# SD_LAN.net
KiCad netlist of a schematic drawn in Altium Designer
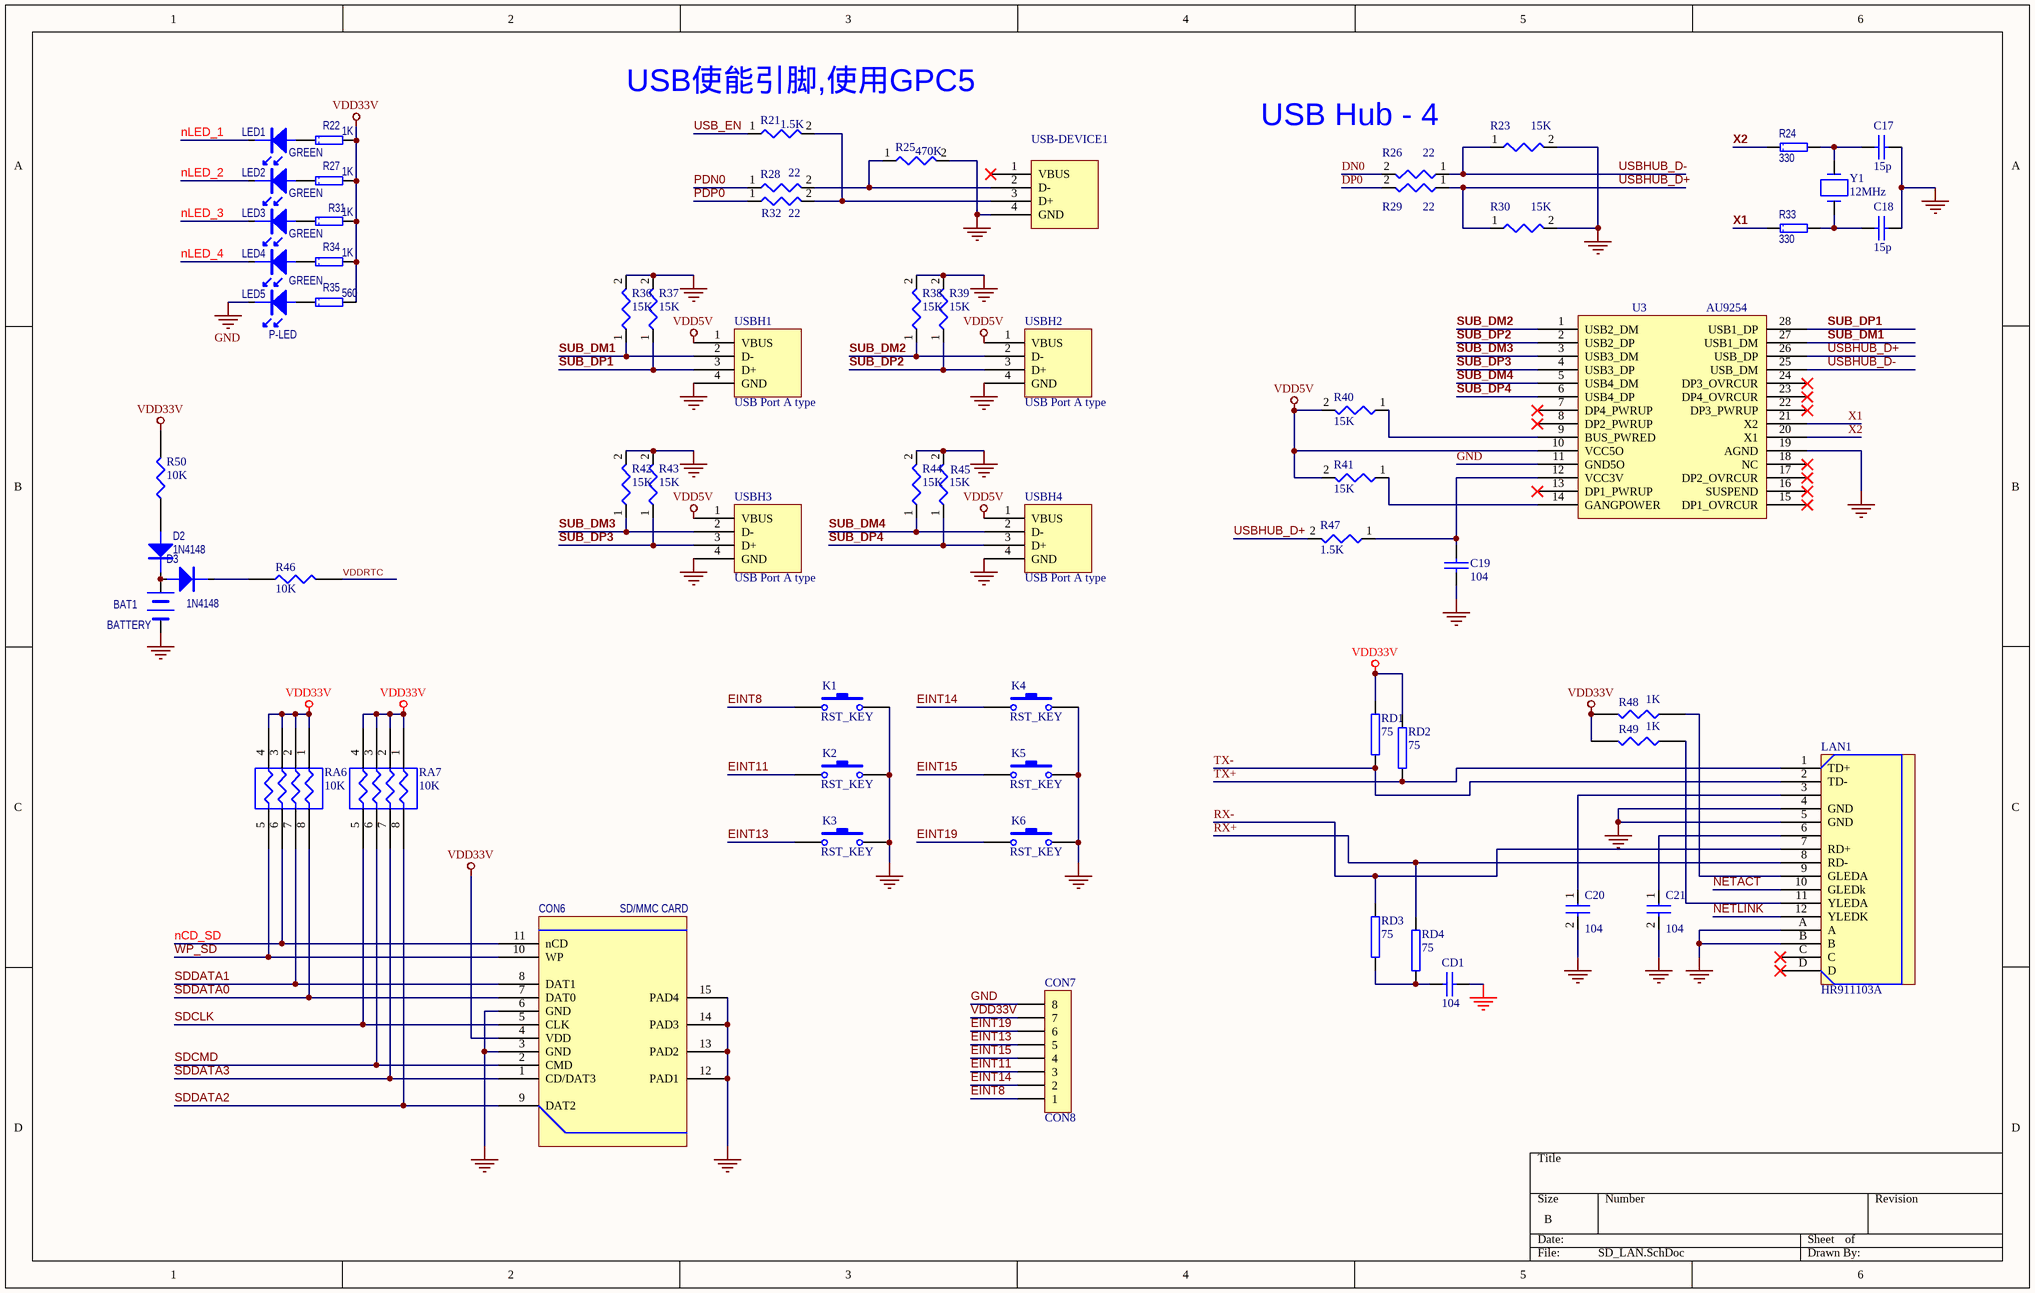
[diagram p0: SD_LAN.SchDoc]

(export (version "E")
  (design (tool "Eeschema 10.0.6"))
  (components
    (comp (ref "BAT1") (value "BATTERY") (footprint "BATT") (libsource (lib "*") (part "BATTERY")))
    (comp (ref "C17") (value "15p") (footprint "0603A") (libsource (lib "*") (part "CAP")))
    (comp (ref "C18") (value "15p") (footprint "0603A") (libsource (lib "*") (part "CAP")))
    (comp (ref "C19") (value "104") (footprint "0603A") (libsource (lib "*") (part "CAP")))
    (comp (ref "C20") (value "104") (footprint "0603A") (libsource (lib "*") (part "CAP NP_0")))
    (comp (ref "C21") (value "104") (footprint "0603A") (libsource (lib "*") (part "CAP NP_0")))
    (comp (ref "CD1") (value "104") (footprint "0603A") (libsource (lib "*") (part "CAP")))
    (comp (ref "CON6") (value "SD/MMC CARD") (footprint "SDCARD") (libsource (lib "*") (part "SD")))
    (comp (ref "CON7")
      (value "CON8")
      (footprint "SMD8")
      (description "Connector")
      (libsource (lib "*") (part "CON8"))
    )
    (comp (ref "D2") (value "1N4148") (footprint "D1206") (libsource (lib "*") (part "DIODE")))
    (comp (ref "D3") (value "1N4148") (footprint "D1206") (libsource (lib "*") (part "DIODE")))
    (comp (ref "K1")
      (value "RST_KEY")
      (footprint "SW-PB2")
      (description "Switch")
      (fields (field (name "PUBLISHER") "Altium Limited"))
      (libsource (lib "Miscellaneous Devices") (part "SW-PB"))
    )
    (comp (ref "K2")
      (value "RST_KEY")
      (footprint "SW-PB2")
      (description "Switch")
      (fields (field (name "PUBLISHER") "Altium Limited"))
      (libsource (lib "Miscellaneous Devices") (part "SW-PB"))
    )
    (comp (ref "K3")
      (value "RST_KEY")
      (footprint "SW-PB2")
      (description "Switch")
      (fields (field (name "PUBLISHER") "Altium Limited"))
      (libsource (lib "Miscellaneous Devices") (part "SW-PB"))
    )
    (comp (ref "K4")
      (value "RST_KEY")
      (footprint "SW-PB2")
      (description "Switch")
      (fields (field (name "PUBLISHER") "Altium Limited"))
      (libsource (lib "Miscellaneous Devices") (part "SW-PB"))
    )
    (comp (ref "K5")
      (value "RST_KEY")
      (footprint "SW-PB2")
      (description "Switch")
      (fields (field (name "PUBLISHER") "Altium Limited"))
      (libsource (lib "Miscellaneous Devices") (part "SW-PB"))
    )
    (comp (ref "K6")
      (value "RST_KEY")
      (footprint "SW-PB2")
      (description "Switch")
      (fields (field (name "PUBLISHER") "Altium Limited"))
      (libsource (lib "Miscellaneous Devices") (part "SW-PB"))
    )
    (comp (ref "LAN1") (value "HR911103A") (footprint "HR911103A") (libsource (lib "*") (part "HR911103A")))
    (comp (ref "LED1") (value "GREEN") (footprint "LED") (libsource (lib "*") (part "LED")))
    (comp (ref "LED2") (value "GREEN") (footprint "LED") (libsource (lib "*") (part "LED")))
    (comp (ref "LED3") (value "GREEN") (footprint "LED") (libsource (lib "*") (part "LED")))
    (comp (ref "LED4") (value "GREEN") (footprint "LED") (libsource (lib "*") (part "LED")))
    (comp (ref "LED5") (value "P-LED") (footprint "LED") (libsource (lib "*") (part "LED")))
    (comp (ref "R21") (value "1.5K") (footprint "0603R") (libsource (lib "*") (part "RESISTOR_2")))
    (comp (ref "R22") (value "1K") (footprint "0603R") (libsource (lib "*") (part "RES")))
    (comp (ref "R23") (value "15K") (footprint "0603R") (libsource (lib "*") (part "RESISTOR_2")))
    (comp (ref "R24") (value "330") (footprint "0603R") (libsource (lib "*") (part "RES")))
    (comp (ref "R25") (value "470K") (footprint "0603R") (libsource (lib "*") (part "RESISTOR_2")))
    (comp (ref "R26") (value "22") (footprint "0603R") (libsource (lib "*") (part "RESISTOR_2")))
    (comp (ref "R27") (value "1K") (footprint "0603R") (libsource (lib "*") (part "RES")))
    (comp (ref "R28") (value "22") (footprint "0603R") (libsource (lib "*") (part "RESISTOR_2")))
    (comp (ref "R29") (value "22") (footprint "0603R") (libsource (lib "*") (part "RESISTOR_2")))
    (comp (ref "R30") (value "15K") (footprint "0603R") (libsource (lib "*") (part "RESISTOR_2")))
    (comp (ref "R31") (value "1K") (footprint "0603R") (libsource (lib "*") (part "RES")))
    (comp (ref "R32") (value "22") (footprint "0603R") (libsource (lib "*") (part "RESISTOR_2")))
    (comp (ref "R33") (value "330") (footprint "0603R") (libsource (lib "*") (part "RES")))
    (comp (ref "R34") (value "1K") (footprint "0603R") (libsource (lib "*") (part "RES")))
    (comp (ref "R35") (value "560") (footprint "0603R") (libsource (lib "*") (part "RES")))
    (comp (ref "R36") (value "15K") (footprint "0603R") (libsource (lib "*") (part "RESISTOR_2")))
    (comp (ref "R37") (value "15K") (footprint "0603R") (libsource (lib "*") (part "RESISTOR_2")))
    (comp (ref "R38") (value "15K") (footprint "0603R") (libsource (lib "*") (part "RESISTOR_2")))
    (comp (ref "R39") (value "15K") (footprint "0603R") (libsource (lib "*") (part "RESISTOR_2")))
    (comp (ref "R40") (value "15K") (footprint "0603R") (libsource (lib "*") (part "RESISTOR_2")))
    (comp (ref "R41") (value "15K") (footprint "0603R") (libsource (lib "*") (part "RESISTOR_2")))
    (comp (ref "R42") (value "15K") (footprint "0603R") (libsource (lib "*") (part "RESISTOR_2")))
    (comp (ref "R43") (value "15K") (footprint "0603R") (libsource (lib "*") (part "RESISTOR_2")))
    (comp (ref "R44") (value "15K") (footprint "0603R") (libsource (lib "*") (part "RESISTOR_2")))
    (comp (ref "R45") (value "15K") (footprint "0603R") (libsource (lib "*") (part "RESISTOR_2")))
    (comp (ref "R46") (value "10K") (footprint "0603R") (libsource (lib "*") (part "RES1")))
    (comp (ref "R47") (value "1.5K") (footprint "0603R") (libsource (lib "*") (part "RESISTOR_2")))
    (comp (ref "R48") (value "1K") (footprint "0603R") (libsource (lib "*") (part "RES1")))
    (comp (ref "R49") (value "1K") (footprint "0603R") (libsource (lib "*") (part "RES1")))
    (comp (ref "R50") (value "10K") (footprint "0603R") (libsource (lib "*") (part "RES1")))
    (comp (ref "RA6") (value "10K") (footprint "R-AR4") (libsource (lib "*") (part "RP4R")))
    (comp (ref "RA7") (value "10K") (footprint "R-AR4") (libsource (lib "*") (part "RP4R")))
    (comp (ref "RD1") (value "75") (footprint "0603R") (libsource (lib "*") (part "RES2")))
    (comp (ref "RD2") (value "75") (footprint "0603R") (libsource (lib "*") (part "RES2")))
    (comp (ref "RD3") (value "75") (footprint "0603R") (libsource (lib "*") (part "RES2")))
    (comp (ref "RD4") (value "75") (footprint "0603R") (libsource (lib "*") (part "RES2")))
    (comp (ref "U3") (value "AU9254") (footprint "AU9254") (libsource (lib "*") (part "USBHUB")))
    (comp (ref "USB-DEVICE1")
      (value "USB Port A type")
      (footprint "USB-B")
      (libsource (lib "*") (part "USBPORT"))
    )
    (comp (ref "USBH1") (value "USB Port A type") (footprint "USB-A") (libsource (lib "*") (part "USBPORT")))
    (comp (ref "USBH2") (value "USB Port A type") (footprint "USB-A") (libsource (lib "*") (part "USBPORT")))
    (comp (ref "USBH3") (value "USB Port A type") (footprint "USB-A") (libsource (lib "*") (part "USBPORT")))
    (comp (ref "USBH4") (value "USB Port A type") (footprint "USB-A") (libsource (lib "*") (part "USBPORT")))
    (comp (ref "Y1") (value "12MHz") (footprint "OSC2PR-1") (libsource (lib "*") (part "CRYSTAL")))
  )
  (nets
    (net (code "1") (name "/DN0") (class "Default")
      (node (ref "R26") (pin "2") (pinfunction "2_2") (pintype "passive"))
    )
    (net (code "2") (name "/DP0") (class "Default")
      (node (ref "R29") (pin "2") (pinfunction "2_2") (pintype "passive"))
    )
    (net (code "3") (name "/EINT8") (class "Default")
      (node (ref "CON7") (pin "1") (pinfunction "1_1") (pintype "passive"))
      (node (ref "K1") (pin "1") (pinfunction "1_1") (pintype "passive"))
    )
    (net (code "4") (name "/EINT11") (class "Default")
      (node (ref "CON7") (pin "3") (pinfunction "3_3") (pintype "passive"))
      (node (ref "K2") (pin "1") (pinfunction "1_1") (pintype "passive"))
    )
    (net (code "5") (name "/EINT13") (class "Default")
      (node (ref "CON7") (pin "5") (pinfunction "5_5") (pintype "passive"))
      (node (ref "K3") (pin "1") (pinfunction "1_1") (pintype "passive"))
    )
    (net (code "6") (name "/EINT14") (class "Default")
      (node (ref "CON7") (pin "2") (pinfunction "2_2") (pintype "passive"))
      (node (ref "K4") (pin "1") (pinfunction "1_1") (pintype "passive"))
    )
    (net (code "7") (name "/EINT15") (class "Default")
      (node (ref "CON7") (pin "4") (pinfunction "4_4") (pintype "passive"))
      (node (ref "K5") (pin "1") (pinfunction "1_1") (pintype "passive"))
    )
    (net (code "8") (name "/EINT19") (class "Default")
      (node (ref "CON7") (pin "6") (pinfunction "6_6") (pintype "passive"))
      (node (ref "K6") (pin "1") (pinfunction "1_1") (pintype "passive"))
    )
    (net (code "9") (name "/NETACT") (class "Default")
      (node (ref "LAN1") (pin "10") (pinfunction "GLEDk_10") (pintype "passive"))
    )
    (net (code "10") (name "/NETLINK") (class "Default")
      (node (ref "LAN1") (pin "12") (pinfunction "YLEDK_12") (pintype "passive"))
    )
    (net (code "11") (name "/PDN0") (class "Default")
      (node (ref "R28") (pin "1") (pinfunction "1_1") (pintype "passive"))
    )
    (net (code "12") (name "/PDP0") (class "Default")
      (node (ref "R32") (pin "1") (pinfunction "1_1") (pintype "passive"))
    )
    (net (code "13") (name "/RX+") (class "Default")
      (node (ref "LAN1") (pin "8") (pinfunction "RD-_8") (pintype "passive"))
      (node (ref "RD4") (pin "2") (pintype "passive"))
    )
    (net (code "14") (name "/RX-") (class "Default")
      (node (ref "LAN1") (pin "7") (pinfunction "RD+_7") (pintype "passive"))
      (node (ref "RD3") (pin "2") (pintype "passive"))
    )
    (net (code "15") (name "/SDCLK") (class "Default")
      (node (ref "CON6") (pin "5") (pinfunction "CLK_5") (pintype "passive"))
      (node (ref "RA7") (pin "5") (pinfunction "R4_5") (pintype "passive"))
    )
    (net (code "16") (name "/SDCMD") (class "Default")
      (node (ref "CON6") (pin "2") (pinfunction "CMD_2") (pintype "passive"))
      (node (ref "RA7") (pin "6") (pinfunction "R3_6") (pintype "passive"))
    )
    (net (code "17") (name "/SDDATA0") (class "Default")
      (node (ref "CON6") (pin "7") (pinfunction "DAT0_7") (pintype "passive"))
      (node (ref "RA6") (pin "8") (pinfunction "R1_8") (pintype "passive"))
    )
    (net (code "18") (name "/SDDATA1") (class "Default")
      (node (ref "CON6") (pin "8") (pinfunction "DAT1_8") (pintype "passive"))
      (node (ref "RA6") (pin "7") (pinfunction "R2_7") (pintype "passive"))
    )
    (net (code "19") (name "/SDDATA2") (class "Default")
      (node (ref "CON6") (pin "9") (pinfunction "DAT2_9") (pintype "passive"))
      (node (ref "RA7") (pin "8") (pinfunction "R1_8") (pintype "passive"))
    )
    (net (code "20") (name "/SDDATA3") (class "Default")
      (node (ref "CON6") (pin "1") (pinfunction "CD/DAT3_1") (pintype "passive"))
      (node (ref "RA7") (pin "7") (pinfunction "R2_7") (pintype "passive"))
    )
    (net (code "21") (name "/SUB_DM1") (class "Default")
      (node (ref "R36") (pin "1") (pinfunction "1_1") (pintype "passive"))
      (node (ref "U3") (pin "27") (pinfunction "USB1_DM_27") (pintype "passive"))
      (node (ref "USBH1") (pin "2") (pinfunction "D-_2") (pintype "passive"))
    )
    (net (code "22") (name "/SUB_DM2") (class "Default")
      (node (ref "R38") (pin "1") (pinfunction "1_1") (pintype "passive"))
      (node (ref "U3") (pin "1") (pinfunction "USB2_DM_1") (pintype "passive"))
      (node (ref "USBH2") (pin "2") (pinfunction "D-_2") (pintype "passive"))
    )
    (net (code "23") (name "/SUB_DM3") (class "Default")
      (node (ref "R42") (pin "1") (pinfunction "1_1") (pintype "passive"))
      (node (ref "U3") (pin "3") (pinfunction "USB3_DM_3") (pintype "passive"))
      (node (ref "USBH3") (pin "2") (pinfunction "D-_2") (pintype "passive"))
    )
    (net (code "24") (name "/SUB_DM4") (class "Default")
      (node (ref "R44") (pin "1") (pinfunction "1_1") (pintype "passive"))
      (node (ref "U3") (pin "5") (pinfunction "USB4_DM_5") (pintype "passive"))
      (node (ref "USBH4") (pin "2") (pinfunction "D-_2") (pintype "passive"))
    )
    (net (code "25") (name "/SUB_DP1") (class "Default")
      (node (ref "R37") (pin "1") (pinfunction "1_1") (pintype "passive"))
      (node (ref "U3") (pin "28") (pinfunction "USB1_DP_28") (pintype "passive"))
      (node (ref "USBH1") (pin "3") (pinfunction "D+_3") (pintype "passive"))
    )
    (net (code "26") (name "/SUB_DP2") (class "Default")
      (node (ref "R39") (pin "1") (pinfunction "1_1") (pintype "passive"))
      (node (ref "U3") (pin "2") (pinfunction "USB2_DP_2") (pintype "passive"))
      (node (ref "USBH2") (pin "3") (pinfunction "D+_3") (pintype "passive"))
    )
    (net (code "27") (name "/SUB_DP3") (class "Default")
      (node (ref "R43") (pin "1") (pinfunction "1_1") (pintype "passive"))
      (node (ref "U3") (pin "4") (pinfunction "USB3_DP_4") (pintype "passive"))
      (node (ref "USBH3") (pin "3") (pinfunction "D+_3") (pintype "passive"))
    )
    (net (code "28") (name "/SUB_DP4") (class "Default")
      (node (ref "R45") (pin "1") (pinfunction "1_1") (pintype "passive"))
      (node (ref "U3") (pin "6") (pinfunction "USB4_DP_6") (pintype "passive"))
      (node (ref "USBH4") (pin "3") (pinfunction "D+_3") (pintype "passive"))
    )
    (net (code "29") (name "/TX+") (class "Default")
      (node (ref "LAN1") (pin "1") (pinfunction "TD+_1") (pintype "passive"))
      (node (ref "RD2") (pin "1") (pintype "passive"))
    )
    (net (code "30") (name "/TX-") (class "Default")
      (node (ref "LAN1") (pin "2") (pinfunction "TD-_2") (pintype "passive"))
      (node (ref "RD1") (pin "1") (pintype "passive"))
    )
    (net (code "31") (name "/USBHUB_D+") (class "Default")
      (node (ref "R29") (pin "1") (pinfunction "1_1") (pintype "passive"))
      (node (ref "R30") (pin "1") (pinfunction "1_1") (pintype "passive"))
      (node (ref "R47") (pin "2") (pinfunction "2_2") (pintype "passive"))
      (node (ref "U3") (pin "26") (pinfunction "USB_DP_26") (pintype "passive"))
    )
    (net (code "32") (name "/USBHUB_D-") (class "Default")
      (node (ref "R23") (pin "1") (pinfunction "1_1") (pintype "passive"))
      (node (ref "R26") (pin "1") (pinfunction "1_1") (pintype "passive"))
      (node (ref "U3") (pin "25") (pinfunction "USB_DM_25") (pintype "passive"))
    )
    (net (code "33") (name "/USB_EN") (class "Default")
      (node (ref "R21") (pin "1") (pinfunction "1_1") (pintype "passive"))
    )
    (net (code "34") (name "/VDDRTC") (class "Default")
      (node (ref "R46") (pin "2") (pinfunction "2_2") (pintype "passive"))
    )
    (net (code "35") (name "/WP_SD") (class "Default")
      (node (ref "CON6") (pin "10") (pinfunction "WP_10") (pintype "passive"))
      (node (ref "RA6") (pin "5") (pinfunction "R4_5") (pintype "passive"))
    )
    (net (code "36") (name "/X1") (class "Default")
      (node (ref "R33") (pin "1") (pinfunction "1_1") (pintype "passive"))
      (node (ref "U3") (pin "21") (pinfunction "X2_21") (pintype "passive"))
    )
    (net (code "37") (name "/X2") (class "Default")
      (node (ref "R24") (pin "1") (pinfunction "1_1") (pintype "passive"))
      (node (ref "U3") (pin "20") (pinfunction "X1_20") (pintype "passive"))
    )
    (net (code "38") (name "/nCD_SD") (class "Default")
      (node (ref "CON6") (pin "11") (pinfunction "nCD_11") (pintype "passive"))
      (node (ref "RA6") (pin "6") (pinfunction "R3_6") (pintype "passive"))
    )
    (net (code "39") (name "/nLED_1") (class "Default")
      (node (ref "LED1") (pin "2") (pinfunction "2_2") (pintype "passive"))
    )
    (net (code "40") (name "/nLED_2") (class "Default")
      (node (ref "LED2") (pin "2") (pinfunction "2_2") (pintype "passive"))
    )
    (net (code "41") (name "/nLED_3") (class "Default")
      (node (ref "LED3") (pin "2") (pinfunction "2_2") (pintype "passive"))
    )
    (net (code "42") (name "/nLED_4") (class "Default")
      (node (ref "LED4") (pin "2") (pinfunction "2_2") (pintype "passive"))
    )
    (net (code "43") (name "GND") (class "Default")
      (node (ref "BAT1") (pin "2") (pintype "passive"))
      (node (ref "C17") (pin "1") (pintype "passive"))
      (node (ref "C18") (pin "1") (pintype "passive"))
      (node (ref "C19") (pin "1") (pintype "passive"))
      (node (ref "C20") (pin "2") (pinfunction "2_2") (pintype "passive"))
      (node (ref "C21") (pin "2") (pinfunction "2_2") (pintype "passive"))
      (node (ref "CD1") (pin "2") (pintype "passive"))
      (node (ref "CON6") (pin "12") (pinfunction "PAD1_12") (pintype "passive"))
      (node (ref "CON6") (pin "13") (pinfunction "PAD2_13") (pintype "passive"))
      (node (ref "CON6") (pin "14") (pinfunction "PAD3_14") (pintype "passive"))
      (node (ref "CON6") (pin "15") (pinfunction "PAD4_15") (pintype "passive"))
      (node (ref "CON6") (pin "3") (pinfunction "GND_3") (pintype "passive"))
      (node (ref "CON6") (pin "6") (pinfunction "GND_6") (pintype "passive"))
      (node (ref "CON7") (pin "8") (pinfunction "8_8") (pintype "passive"))
      (node (ref "K1") (pin "2") (pinfunction "2_2") (pintype "passive"))
      (node (ref "K2") (pin "2") (pinfunction "2_2") (pintype "passive"))
      (node (ref "K3") (pin "2") (pinfunction "2_2") (pintype "passive"))
      (node (ref "K4") (pin "2") (pinfunction "2_2") (pintype "passive"))
      (node (ref "K5") (pin "2") (pinfunction "2_2") (pintype "passive"))
      (node (ref "K6") (pin "2") (pinfunction "2_2") (pintype "passive"))
      (node (ref "LAN1") (pin "4") (pinfunction "GND_4") (pintype "passive"))
      (node (ref "LAN1") (pin "5") (pinfunction "GND_5") (pintype "passive"))
      (node (ref "LAN1") (pin "A") (pinfunction "A_A") (pintype "passive"))
      (node (ref "LAN1") (pin "B") (pinfunction "B_B") (pintype "passive"))
      (node (ref "LED5") (pin "2") (pinfunction "2_2") (pintype "passive"))
      (node (ref "R23") (pin "2") (pinfunction "2_2") (pintype "passive"))
      (node (ref "R25") (pin "2") (pinfunction "2_2") (pintype "passive"))
      (node (ref "R30") (pin "2") (pinfunction "2_2") (pintype "passive"))
      (node (ref "R36") (pin "2") (pinfunction "2_2") (pintype "passive"))
      (node (ref "R37") (pin "2") (pinfunction "2_2") (pintype "passive"))
      (node (ref "R38") (pin "2") (pinfunction "2_2") (pintype "passive"))
      (node (ref "R39") (pin "2") (pinfunction "2_2") (pintype "passive"))
      (node (ref "R42") (pin "2") (pinfunction "2_2") (pintype "passive"))
      (node (ref "R43") (pin "2") (pinfunction "2_2") (pintype "passive"))
      (node (ref "R44") (pin "2") (pinfunction "2_2") (pintype "passive"))
      (node (ref "R45") (pin "2") (pinfunction "2_2") (pintype "passive"))
      (node (ref "U3") (pin "11") (pinfunction "GND5O_11") (pintype "passive"))
      (node (ref "U3") (pin "19") (pinfunction "AGND_19") (pintype "passive"))
      (node (ref "USB-DEVICE1") (pin "4") (pinfunction "GND_4") (pintype "passive"))
      (node (ref "USBH1") (pin "4") (pinfunction "GND_4") (pintype "passive"))
      (node (ref "USBH2") (pin "4") (pinfunction "GND_4") (pintype "passive"))
      (node (ref "USBH3") (pin "4") (pinfunction "GND_4") (pintype "passive"))
      (node (ref "USBH4") (pin "4") (pinfunction "GND_4") (pintype "passive"))
    )
    (net (code "44") (name "Net-(BAT1-Pad1)") (class "Default")
      (node (ref "BAT1") (pin "1") (pintype "passive"))
      (node (ref "D2") (pin "2") (pinfunction "2_2") (pintype "passive"))
      (node (ref "D3") (pin "1") (pinfunction "1_1") (pintype "passive"))
    )
    (net (code "45") (name "Net-(C17-Pad2)") (class "Default")
      (node (ref "C17") (pin "2") (pintype "passive"))
      (node (ref "R24") (pin "2") (pinfunction "2_2") (pintype "passive"))
      (node (ref "Y1") (pin "1") (pinfunction "1_1") (pintype "passive"))
    )
    (net (code "46") (name "Net-(C18-Pad2)") (class "Default")
      (node (ref "C18") (pin "2") (pintype "passive"))
      (node (ref "R33") (pin "2") (pinfunction "2_2") (pintype "passive"))
      (node (ref "Y1") (pin "2") (pinfunction "2_2") (pintype "passive"))
    )
    (net (code "47") (name "Net-(C20-Pad1)") (class "Default")
      (node (ref "C20") (pin "1") (pinfunction "1_1") (pintype "passive"))
      (node (ref "LAN1") (pin "3") (pintype "passive"))
    )
    (net (code "48") (name "Net-(C21-Pad1)") (class "Default")
      (node (ref "C21") (pin "1") (pinfunction "1_1") (pintype "passive"))
      (node (ref "LAN1") (pin "6") (pintype "passive"))
    )
    (net (code "49") (name "Net-(CD1-Pad1)") (class "Default")
      (node (ref "CD1") (pin "1") (pintype "passive"))
      (node (ref "RD3") (pin "1") (pintype "passive"))
      (node (ref "RD4") (pin "1") (pintype "passive"))
    )
    (net (code "50") (name "Net-(D2-Pad1)") (class "Default")
      (node (ref "D2") (pin "1") (pinfunction "1_1") (pintype "passive"))
      (node (ref "R50") (pin "1") (pinfunction "1_1") (pintype "passive"))
    )
    (net (code "51") (name "Net-(D3-Pad2)") (class "Default")
      (node (ref "D3") (pin "2") (pinfunction "2_2") (pintype "passive"))
      (node (ref "R46") (pin "1") (pinfunction "1_1") (pintype "passive"))
    )
    (net (code "52") (name "Net-(LAN1-GLEDA)") (class "Default")
      (node (ref "LAN1") (pin "9") (pinfunction "GLEDA_9") (pintype "passive"))
      (node (ref "R48") (pin "1") (pinfunction "1_1") (pintype "passive"))
    )
    (net (code "53") (name "Net-(LAN1-YLEDA)") (class "Default")
      (node (ref "LAN1") (pin "11") (pinfunction "YLEDA_11") (pintype "passive"))
      (node (ref "R49") (pin "1") (pinfunction "1_1") (pintype "passive"))
    )
    (net (code "54") (name "Net-(LED1-Pad1)") (class "Default")
      (node (ref "LED1") (pin "1") (pinfunction "1_1") (pintype "passive"))
      (node (ref "R22") (pin "1") (pinfunction "1_1") (pintype "passive"))
    )
    (net (code "55") (name "Net-(LED2-Pad1)") (class "Default")
      (node (ref "LED2") (pin "1") (pinfunction "1_1") (pintype "passive"))
      (node (ref "R27") (pin "1") (pinfunction "1_1") (pintype "passive"))
    )
    (net (code "56") (name "Net-(LED3-Pad1)") (class "Default")
      (node (ref "LED3") (pin "1") (pinfunction "1_1") (pintype "passive"))
      (node (ref "R31") (pin "1") (pinfunction "1_1") (pintype "passive"))
    )
    (net (code "57") (name "Net-(LED4-Pad1)") (class "Default")
      (node (ref "LED4") (pin "1") (pinfunction "1_1") (pintype "passive"))
      (node (ref "R34") (pin "1") (pinfunction "1_1") (pintype "passive"))
    )
    (net (code "58") (name "Net-(LED5-Pad1)") (class "Default")
      (node (ref "LED5") (pin "1") (pinfunction "1_1") (pintype "passive"))
      (node (ref "R35") (pin "1") (pinfunction "1_1") (pintype "passive"))
    )
    (net (code "59") (name "Net-(U3-BUS_PWRED)") (class "Default")
      (node (ref "R40") (pin "1") (pinfunction "1_1") (pintype "passive"))
      (node (ref "U3") (pin "9") (pinfunction "BUS_PWRED_9") (pintype "passive"))
    )
    (net (code "60") (name "Net-(U3-GANGPOWER)") (class "Default")
      (node (ref "R41") (pin "1") (pinfunction "1_1") (pintype "passive"))
      (node (ref "U3") (pin "14") (pinfunction "GANGPOWER_14") (pintype "passive"))
    )
    (net (code "61") (name "Net-(U3-VCC3V)") (class "Default")
      (node (ref "C19") (pin "2") (pintype "passive"))
      (node (ref "R47") (pin "1") (pinfunction "1_1") (pintype "passive"))
      (node (ref "U3") (pin "12") (pinfunction "VCC3V_12") (pintype "passive"))
    )
    (net (code "62") (name "Net-(USB-DEVICE1-D+)") (class "Default")
      (node (ref "R21") (pin "2") (pinfunction "2_2") (pintype "passive"))
      (node (ref "R32") (pin "2") (pinfunction "2_2") (pintype "passive"))
      (node (ref "USB-DEVICE1") (pin "3") (pinfunction "D+_3") (pintype "passive"))
    )
    (net (code "63") (name "Net-(USB-DEVICE1-D-)") (class "Default")
      (node (ref "R25") (pin "1") (pinfunction "1_1") (pintype "passive"))
      (node (ref "R28") (pin "2") (pinfunction "2_2") (pintype "passive"))
      (node (ref "USB-DEVICE1") (pin "2") (pinfunction "D-_2") (pintype "passive"))
    )
    (net (code "64") (name "VDD5V") (class "Default")
      (node (ref "R40") (pin "2") (pinfunction "2_2") (pintype "passive"))
      (node (ref "R41") (pin "2") (pinfunction "2_2") (pintype "passive"))
      (node (ref "U3") (pin "10") (pinfunction "VCC5O_10") (pintype "passive"))
      (node (ref "USBH1") (pin "1") (pinfunction "VBUS_1") (pintype "passive"))
      (node (ref "USBH2") (pin "1") (pinfunction "VBUS_1") (pintype "passive"))
      (node (ref "USBH3") (pin "1") (pinfunction "VBUS_1") (pintype "passive"))
      (node (ref "USBH4") (pin "1") (pinfunction "VBUS_1") (pintype "passive"))
    )
    (net (code "65") (name "VDD33V") (class "Default")
      (node (ref "CON6") (pin "4") (pinfunction "VDD_4") (pintype "passive"))
      (node (ref "CON7") (pin "7") (pinfunction "7_7") (pintype "passive"))
      (node (ref "R22") (pin "2") (pinfunction "2_2") (pintype "passive"))
      (node (ref "R27") (pin "2") (pinfunction "2_2") (pintype "passive"))
      (node (ref "R31") (pin "2") (pinfunction "2_2") (pintype "passive"))
      (node (ref "R34") (pin "2") (pinfunction "2_2") (pintype "passive"))
      (node (ref "R35") (pin "2") (pinfunction "2_2") (pintype "passive"))
      (node (ref "R48") (pin "2") (pinfunction "2_2") (pintype "passive"))
      (node (ref "R49") (pin "2") (pinfunction "2_2") (pintype "passive"))
      (node (ref "R50") (pin "2") (pinfunction "2_2") (pintype "passive"))
      (node (ref "RA6") (pin "1") (pinfunction "R1_1") (pintype "passive"))
      (node (ref "RA6") (pin "2") (pinfunction "R2_2") (pintype "passive"))
      (node (ref "RA6") (pin "3") (pinfunction "R3_3") (pintype "passive"))
      (node (ref "RA6") (pin "4") (pinfunction "R4_4") (pintype "passive"))
      (node (ref "RA7") (pin "1") (pinfunction "R1_1") (pintype "passive"))
      (node (ref "RA7") (pin "2") (pinfunction "R2_2") (pintype "passive"))
      (node (ref "RA7") (pin "3") (pinfunction "R3_3") (pintype "passive"))
      (node (ref "RA7") (pin "4") (pinfunction "R4_4") (pintype "passive"))
      (node (ref "RD1") (pin "2") (pintype "passive"))
      (node (ref "RD2") (pin "2") (pintype "passive"))
    )
    (net (code "66") (name "unconnected-(LAN1-PadC)") (class "Default")
      (node (ref "LAN1") (pin "C") (pinfunction "C_C") (pintype "passive+no_connect"))
    )
    (net (code "67") (name "unconnected-(LAN1-PadD)") (class "Default")
      (node (ref "LAN1") (pin "D") (pinfunction "D_D") (pintype "passive+no_connect"))
    )
    (net (code "68") (name "unconnected-(U3-DP1_OVRCUR-Pad15)") (class "Default")
      (node (ref "U3") (pin "15") (pinfunction "DP1_OVRCUR_15") (pintype "passive+no_connect"))
    )
    (net (code "69") (name "unconnected-(U3-DP1_PWRUP-Pad13)") (class "Default")
      (node (ref "U3") (pin "13") (pinfunction "DP1_PWRUP_13") (pintype "passive+no_connect"))
    )
    (net (code "70") (name "unconnected-(U3-DP2_OVRCUR-Pad17)") (class "Default")
      (node (ref "U3") (pin "17") (pinfunction "DP2_OVRCUR_17") (pintype "passive+no_connect"))
    )
    (net (code "71") (name "unconnected-(U3-DP2_PWRUP-Pad8)") (class "Default")
      (node (ref "U3") (pin "8") (pinfunction "DP2_PWRUP_8") (pintype "passive+no_connect"))
    )
    (net (code "72") (name "unconnected-(U3-DP3_OVRCUR-Pad24)") (class "Default")
      (node (ref "U3") (pin "24") (pinfunction "DP3_OVRCUR_24") (pintype "passive+no_connect"))
    )
    (net (code "73") (name "unconnected-(U3-DP3_PWRUP-Pad22)") (class "Default")
      (node (ref "U3") (pin "22") (pinfunction "DP3_PWRUP_22") (pintype "passive+no_connect"))
    )
    (net (code "74") (name "unconnected-(U3-DP4_OVRCUR-Pad23)") (class "Default")
      (node (ref "U3") (pin "23") (pinfunction "DP4_OVRCUR_23") (pintype "passive+no_connect"))
    )
    (net (code "75") (name "unconnected-(U3-DP4_PWRUP-Pad7)") (class "Default")
      (node (ref "U3") (pin "7") (pinfunction "DP4_PWRUP_7") (pintype "passive+no_connect"))
    )
    (net (code "76") (name "unconnected-(U3-NC-Pad18)") (class "Default")
      (node (ref "U3") (pin "18") (pinfunction "NC_18") (pintype "passive+no_connect"))
    )
    (net (code "77") (name "unconnected-(U3-SUSPEND-Pad16)") (class "Default")
      (node (ref "U3") (pin "16") (pinfunction "SUSPEND_16") (pintype "passive+no_connect"))
    )
    (net (code "78") (name "unconnected-(USB-DEVICE1-VBUS-Pad1)") (class "Default")
      (node (ref "USB-DEVICE1") (pin "1") (pinfunction "VBUS_1") (pintype "passive+no_connect"))
    )
  )
)
